# new_moisture_ckt_design.net
KiCad netlist of a schematic drawn in EAGLE
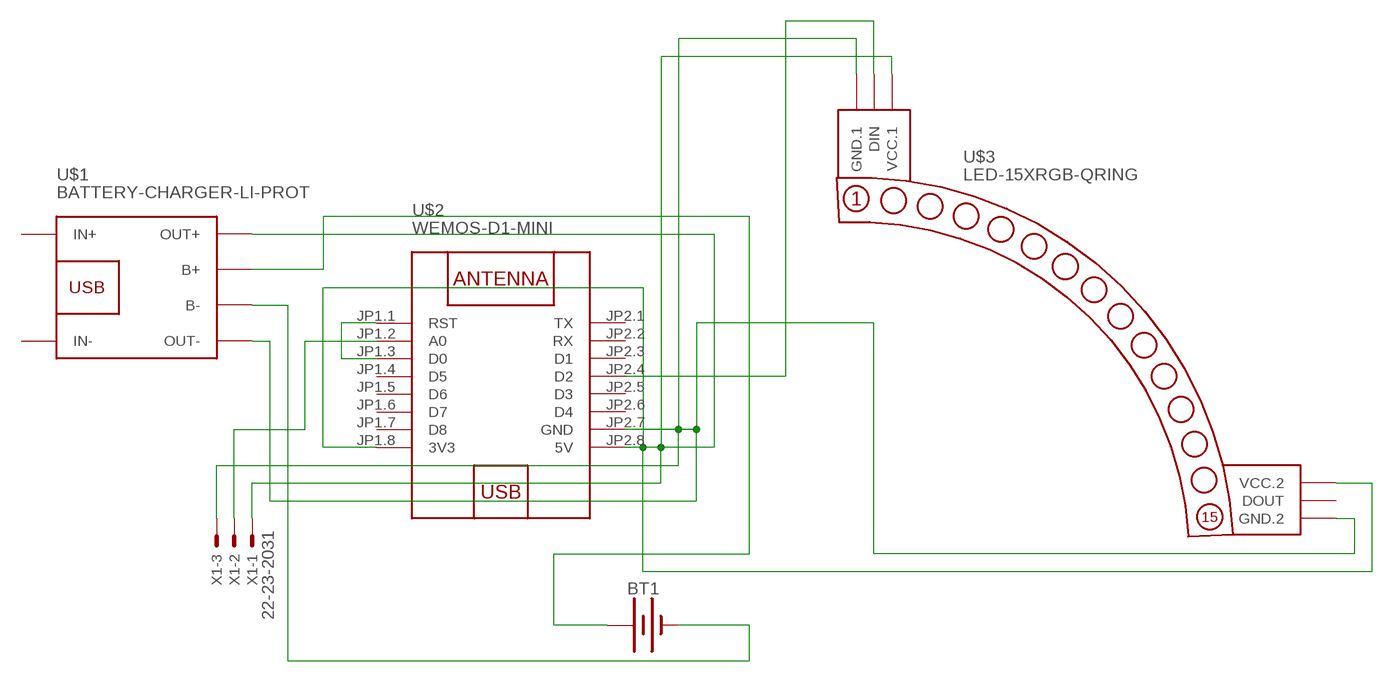
[diagram p0: schematic, sheet 1]

(export (version "E")
  (design (tool "Eeschema 10.0.6"))
  (components
    (comp (ref "BT1")
      (value "BATTERY-12MM_PTH")
      (footprint "eagle-import:BATTCON_12MM_PTH")
      (libsource (lib "eagle-import") (part "BATTERY-12MM_PTH"))
    )
    (comp (ref "U$1")
      (value "BATTERY-CHARGER-LI-PROT")
      (footprint "eagle-import:BATTERY-CHARGER-LI-PROT")
      (libsource (lib "eagle-import") (part "BATTERY-CHARGER-LI-PROT"))
    )
    (comp (ref "U$2")
      (value "WEMOS-D1-MINI")
      (footprint "eagle-import:WEMOS-D1-MINI")
      (libsource (lib "eagle-import") (part "WEMOS-D1-MINI"))
    )
    (comp (ref "U$3")
      (value "LED-15XRGB-QRING")
      (footprint "eagle-import:LED-15XRGB-QRING")
      (libsource (lib "eagle-import") (part "LED-15XRGB-QRING"))
    )
    (comp (ref "X1")
      (value "22-23-2031")
      (footprint "eagle-import:22-23-2031")
      (fields (field (name "MF") "MOLEX"))
      (libsource (lib "eagle-import") (part "22-23-2031"))
    )
  )
  (nets
    (net (code "1") (name "Net-(BT1-+)") (class "Default")
      (node (ref "BT1") (pin "VCC@1") (pinfunction "+_VCC@1") (pintype "power_in"))
      (node (ref "U$1") (pin "B+") (pinfunction "B+_B+") (pintype "bidirectional"))
    )
    (net (code "2") (name "Net-(BT1--)") (class "Default")
      (node (ref "BT1") (pin "GND") (pinfunction "-_GND") (pintype "power_in"))
      (node (ref "U$1") (pin "B-") (pinfunction "B-_B-") (pintype "bidirectional"))
    )
    (net (code "3") (name "Net-(U$2-3V3)") (class "Default")
      (node (ref "U$1") (pin "OUT+") (pinfunction "OUT+_OUT+") (pintype "bidirectional"))
      (node (ref "U$2") (pin "JP1.8") (pinfunction "3V3_JP1.8") (pintype "power_in"))
      (node (ref "U$2") (pin "JP2.8") (pinfunction "5V_JP2.8") (pintype "power_in"))
      (node (ref "U$3") (pin "3") (pinfunction "VCC.1_3") (pintype "power_in"))
      (node (ref "U$3") (pin "6") (pinfunction "VCC.2_6") (pintype "power_in"))
      (node (ref "X1") (pin "1") (pinfunction "S_1") (pintype "passive"))
    )
    (net (code "4") (name "Net-(U$2-A0)") (class "Default")
      (node (ref "U$2") (pin "JP1.2") (pinfunction "A0_JP1.2") (pintype "bidirectional"))
      (node (ref "X1") (pin "2") (pinfunction "S_2") (pintype "passive"))
    )
    (net (code "5") (name "Net-(U$2-D0)") (class "Default")
      (node (ref "U$2") (pin "JP1.1") (pinfunction "RST_JP1.1") (pintype "bidirectional"))
      (node (ref "U$2") (pin "JP1.3") (pinfunction "D0_JP1.3") (pintype "bidirectional"))
    )
    (net (code "6") (name "Net-(U$2-D2)") (class "Default")
      (node (ref "U$2") (pin "JP2.4") (pinfunction "D2_JP2.4") (pintype "bidirectional"))
      (node (ref "U$3") (pin "2") (pinfunction "DIN_2") (pintype "input"))
    )
    (net (code "7") (name "Net-(U$2-GND)") (class "Default")
      (node (ref "U$1") (pin "OUT-") (pinfunction "OUT-_OUT-") (pintype "bidirectional"))
      (node (ref "U$2") (pin "JP2.7") (pinfunction "GND_JP2.7") (pintype "power_in"))
      (node (ref "U$3") (pin "1") (pinfunction "GND.1_1") (pintype "power_in"))
      (node (ref "U$3") (pin "4") (pinfunction "GND.2_4") (pintype "power_in"))
      (node (ref "X1") (pin "3") (pinfunction "S_3") (pintype "passive"))
    )
    (net (code "8") (name "unconnected-(U$1-PadIN+)") (class "Default")
      (node (ref "U$1") (pin "IN+") (pinfunction "IN+_IN+") (pintype "bidirectional"))
    )
    (net (code "9") (name "unconnected-(U$1-PadIN-)") (class "Default")
      (node (ref "U$1") (pin "IN-") (pinfunction "IN-_IN-") (pintype "bidirectional"))
    )
    (net (code "10") (name "unconnected-(U$2-D1-PadJP2.3)") (class "Default")
      (node (ref "U$2") (pin "JP2.3") (pinfunction "D1_JP2.3") (pintype "bidirectional"))
    )
    (net (code "11") (name "unconnected-(U$2-D3-PadJP2.5)") (class "Default")
      (node (ref "U$2") (pin "JP2.5") (pinfunction "D3_JP2.5") (pintype "bidirectional"))
    )
    (net (code "12") (name "unconnected-(U$2-D4-PadJP2.6)") (class "Default")
      (node (ref "U$2") (pin "JP2.6") (pinfunction "D4_JP2.6") (pintype "bidirectional"))
    )
    (net (code "13") (name "unconnected-(U$2-D5-PadJP1.4)") (class "Default")
      (node (ref "U$2") (pin "JP1.4") (pinfunction "D5_JP1.4") (pintype "bidirectional"))
    )
    (net (code "14") (name "unconnected-(U$2-D6-PadJP1.5)") (class "Default")
      (node (ref "U$2") (pin "JP1.5") (pinfunction "D6_JP1.5") (pintype "bidirectional"))
    )
    (net (code "15") (name "unconnected-(U$2-D7-PadJP1.6)") (class "Default")
      (node (ref "U$2") (pin "JP1.6") (pinfunction "D7_JP1.6") (pintype "bidirectional"))
    )
    (net (code "16") (name "unconnected-(U$2-D8-PadJP1.7)") (class "Default")
      (node (ref "U$2") (pin "JP1.7") (pinfunction "D8_JP1.7") (pintype "bidirectional"))
    )
    (net (code "17") (name "unconnected-(U$2-RX-PadJP2.2)") (class "Default")
      (node (ref "U$2") (pin "JP2.2") (pinfunction "RX_JP2.2") (pintype "bidirectional"))
    )
    (net (code "18") (name "unconnected-(U$2-TX-PadJP2.1)") (class "Default")
      (node (ref "U$2") (pin "JP2.1") (pinfunction "TX_JP2.1") (pintype "bidirectional"))
    )
    (net (code "19") (name "unconnected-(U$3-DOUT-Pad5)") (class "Default")
      (node (ref "U$3") (pin "5") (pinfunction "DOUT_5") (pintype "output"))
    )
  )
)
